# ShematicPCB.net
KiCad netlist of a schematic drawn in EAGLE
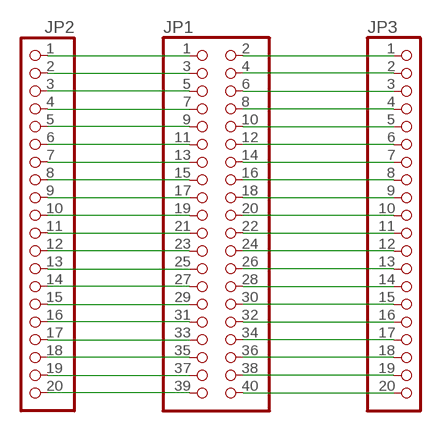
[diagram p0: schematic, sheet 1]

(export (version "E")
  (design (tool "Eeschema 10.0.6"))
  (components
    (comp (ref "JP1")
      (value "PINHD-2X20")
      (footprint "eagle-import:2X20")
      (libsource (lib "eagle-import") (part "PINHD-2X20"))
    )
    (comp (ref "JP2")
      (value "PINHD-1X20")
      (footprint "eagle-import:1X20")
      (libsource (lib "eagle-import") (part "PINHD-1X20"))
    )
    (comp (ref "JP3")
      (value "PINHD-1X20")
      (footprint "eagle-import:1X20")
      (libsource (lib "eagle-import") (part "PINHD-1X20"))
    )
  )
  (nets
    (net (code "1") (name "Net-(JP1-Pad1)") (class "Default")
      (node (ref "JP1") (pin "1") (pinfunction "1_1") (pintype "passive"))
      (node (ref "JP2") (pin "1") (pinfunction "1_1") (pintype "passive"))
    )
    (net (code "2") (name "Net-(JP1-Pad2)") (class "Default")
      (node (ref "JP1") (pin "2") (pinfunction "2_2") (pintype "passive"))
      (node (ref "JP3") (pin "1") (pinfunction "1_1") (pintype "passive"))
    )
    (net (code "3") (name "Net-(JP1-Pad3)") (class "Default")
      (node (ref "JP1") (pin "3") (pinfunction "3_3") (pintype "passive"))
      (node (ref "JP2") (pin "2") (pinfunction "2_2") (pintype "passive"))
    )
    (net (code "4") (name "Net-(JP1-Pad4)") (class "Default")
      (node (ref "JP1") (pin "4") (pinfunction "4_4") (pintype "passive"))
      (node (ref "JP3") (pin "2") (pinfunction "2_2") (pintype "passive"))
    )
    (net (code "5") (name "Net-(JP1-Pad5)") (class "Default")
      (node (ref "JP1") (pin "5") (pinfunction "5_5") (pintype "passive"))
      (node (ref "JP2") (pin "3") (pinfunction "3_3") (pintype "passive"))
    )
    (net (code "6") (name "Net-(JP1-Pad6)") (class "Default")
      (node (ref "JP1") (pin "6") (pinfunction "6_6") (pintype "passive"))
      (node (ref "JP3") (pin "3") (pinfunction "3_3") (pintype "passive"))
    )
    (net (code "7") (name "Net-(JP1-Pad7)") (class "Default")
      (node (ref "JP1") (pin "7") (pinfunction "7_7") (pintype "passive"))
      (node (ref "JP2") (pin "4") (pinfunction "4_4") (pintype "passive"))
    )
    (net (code "8") (name "Net-(JP1-Pad8)") (class "Default")
      (node (ref "JP1") (pin "8") (pinfunction "8_8") (pintype "passive"))
      (node (ref "JP3") (pin "4") (pinfunction "4_4") (pintype "passive"))
    )
    (net (code "9") (name "Net-(JP1-Pad9)") (class "Default")
      (node (ref "JP1") (pin "9") (pinfunction "9_9") (pintype "passive"))
      (node (ref "JP2") (pin "5") (pinfunction "5_5") (pintype "passive"))
    )
    (net (code "10") (name "Net-(JP1-Pad10)") (class "Default")
      (node (ref "JP1") (pin "10") (pinfunction "10_10") (pintype "passive"))
      (node (ref "JP3") (pin "5") (pinfunction "5_5") (pintype "passive"))
    )
    (net (code "11") (name "Net-(JP1-Pad11)") (class "Default")
      (node (ref "JP1") (pin "11") (pinfunction "11_11") (pintype "passive"))
      (node (ref "JP2") (pin "6") (pinfunction "6_6") (pintype "passive"))
    )
    (net (code "12") (name "Net-(JP1-Pad12)") (class "Default")
      (node (ref "JP1") (pin "12") (pinfunction "12_12") (pintype "passive"))
      (node (ref "JP3") (pin "6") (pinfunction "6_6") (pintype "passive"))
    )
    (net (code "13") (name "Net-(JP1-Pad13)") (class "Default")
      (node (ref "JP1") (pin "13") (pinfunction "13_13") (pintype "passive"))
      (node (ref "JP2") (pin "7") (pinfunction "7_7") (pintype "passive"))
    )
    (net (code "14") (name "Net-(JP1-Pad14)") (class "Default")
      (node (ref "JP1") (pin "14") (pinfunction "14_14") (pintype "passive"))
      (node (ref "JP3") (pin "7") (pinfunction "7_7") (pintype "passive"))
    )
    (net (code "15") (name "Net-(JP1-Pad15)") (class "Default")
      (node (ref "JP1") (pin "15") (pinfunction "15_15") (pintype "passive"))
      (node (ref "JP2") (pin "8") (pinfunction "8_8") (pintype "passive"))
    )
    (net (code "16") (name "Net-(JP1-Pad16)") (class "Default")
      (node (ref "JP1") (pin "16") (pinfunction "16_16") (pintype "passive"))
      (node (ref "JP3") (pin "8") (pinfunction "8_8") (pintype "passive"))
    )
    (net (code "17") (name "Net-(JP1-Pad17)") (class "Default")
      (node (ref "JP1") (pin "17") (pinfunction "17_17") (pintype "passive"))
      (node (ref "JP2") (pin "9") (pinfunction "9_9") (pintype "passive"))
    )
    (net (code "18") (name "Net-(JP1-Pad18)") (class "Default")
      (node (ref "JP1") (pin "18") (pinfunction "18_18") (pintype "passive"))
      (node (ref "JP3") (pin "9") (pinfunction "9_9") (pintype "passive"))
    )
    (net (code "19") (name "Net-(JP1-Pad19)") (class "Default")
      (node (ref "JP1") (pin "19") (pinfunction "19_19") (pintype "passive"))
      (node (ref "JP2") (pin "10") (pinfunction "10_10") (pintype "passive"))
    )
    (net (code "20") (name "Net-(JP1-Pad20)") (class "Default")
      (node (ref "JP1") (pin "20") (pinfunction "20_20") (pintype "passive"))
      (node (ref "JP3") (pin "10") (pinfunction "10_10") (pintype "passive"))
    )
    (net (code "21") (name "Net-(JP1-Pad21)") (class "Default")
      (node (ref "JP1") (pin "21") (pinfunction "21_21") (pintype "passive"))
      (node (ref "JP2") (pin "11") (pinfunction "11_11") (pintype "passive"))
    )
    (net (code "22") (name "Net-(JP1-Pad22)") (class "Default")
      (node (ref "JP1") (pin "22") (pinfunction "22_22") (pintype "passive"))
      (node (ref "JP3") (pin "11") (pinfunction "11_11") (pintype "passive"))
    )
    (net (code "23") (name "Net-(JP1-Pad23)") (class "Default")
      (node (ref "JP1") (pin "23") (pinfunction "23_23") (pintype "passive"))
      (node (ref "JP2") (pin "12") (pinfunction "12_12") (pintype "passive"))
    )
    (net (code "24") (name "Net-(JP1-Pad24)") (class "Default")
      (node (ref "JP1") (pin "24") (pinfunction "24_24") (pintype "passive"))
      (node (ref "JP3") (pin "12") (pinfunction "12_12") (pintype "passive"))
    )
    (net (code "25") (name "Net-(JP1-Pad25)") (class "Default")
      (node (ref "JP1") (pin "25") (pinfunction "25_25") (pintype "passive"))
      (node (ref "JP2") (pin "13") (pinfunction "13_13") (pintype "passive"))
    )
    (net (code "26") (name "Net-(JP1-Pad26)") (class "Default")
      (node (ref "JP1") (pin "26") (pinfunction "26_26") (pintype "passive"))
      (node (ref "JP3") (pin "13") (pinfunction "13_13") (pintype "passive"))
    )
    (net (code "27") (name "Net-(JP1-Pad27)") (class "Default")
      (node (ref "JP1") (pin "27") (pinfunction "27_27") (pintype "passive"))
      (node (ref "JP2") (pin "14") (pinfunction "14_14") (pintype "passive"))
    )
    (net (code "28") (name "Net-(JP1-Pad28)") (class "Default")
      (node (ref "JP1") (pin "28") (pinfunction "28_28") (pintype "passive"))
      (node (ref "JP3") (pin "14") (pinfunction "14_14") (pintype "passive"))
    )
    (net (code "29") (name "Net-(JP1-Pad29)") (class "Default")
      (node (ref "JP1") (pin "29") (pinfunction "29_29") (pintype "passive"))
      (node (ref "JP2") (pin "15") (pinfunction "15_15") (pintype "passive"))
    )
    (net (code "30") (name "Net-(JP1-Pad30)") (class "Default")
      (node (ref "JP1") (pin "30") (pinfunction "30_30") (pintype "passive"))
      (node (ref "JP3") (pin "15") (pinfunction "15_15") (pintype "passive"))
    )
    (net (code "31") (name "Net-(JP1-Pad31)") (class "Default")
      (node (ref "JP1") (pin "31") (pinfunction "31_31") (pintype "passive"))
      (node (ref "JP2") (pin "16") (pinfunction "16_16") (pintype "passive"))
    )
    (net (code "32") (name "Net-(JP1-Pad32)") (class "Default")
      (node (ref "JP1") (pin "32") (pinfunction "32_32") (pintype "passive"))
      (node (ref "JP3") (pin "16") (pinfunction "16_16") (pintype "passive"))
    )
    (net (code "33") (name "Net-(JP1-Pad33)") (class "Default")
      (node (ref "JP1") (pin "33") (pinfunction "33_33") (pintype "passive"))
      (node (ref "JP2") (pin "17") (pinfunction "17_17") (pintype "passive"))
    )
    (net (code "34") (name "Net-(JP1-Pad34)") (class "Default")
      (node (ref "JP1") (pin "34") (pinfunction "34_34") (pintype "passive"))
      (node (ref "JP3") (pin "17") (pinfunction "17_17") (pintype "passive"))
    )
    (net (code "35") (name "Net-(JP1-Pad35)") (class "Default")
      (node (ref "JP1") (pin "35") (pinfunction "35_35") (pintype "passive"))
      (node (ref "JP2") (pin "18") (pinfunction "18_18") (pintype "passive"))
    )
    (net (code "36") (name "Net-(JP1-Pad36)") (class "Default")
      (node (ref "JP1") (pin "36") (pinfunction "36_36") (pintype "passive"))
      (node (ref "JP3") (pin "18") (pinfunction "18_18") (pintype "passive"))
    )
    (net (code "37") (name "Net-(JP1-Pad37)") (class "Default")
      (node (ref "JP1") (pin "37") (pinfunction "37_37") (pintype "passive"))
      (node (ref "JP2") (pin "19") (pinfunction "19_19") (pintype "passive"))
    )
    (net (code "38") (name "Net-(JP1-Pad38)") (class "Default")
      (node (ref "JP1") (pin "38") (pinfunction "38_38") (pintype "passive"))
      (node (ref "JP3") (pin "19") (pinfunction "19_19") (pintype "passive"))
    )
    (net (code "39") (name "Net-(JP1-Pad39)") (class "Default")
      (node (ref "JP1") (pin "39") (pinfunction "39_39") (pintype "passive"))
      (node (ref "JP2") (pin "20") (pinfunction "20_20") (pintype "passive"))
    )
    (net (code "40") (name "Net-(JP1-Pad40)") (class "Default")
      (node (ref "JP1") (pin "40") (pinfunction "40_40") (pintype "passive"))
      (node (ref "JP3") (pin "20") (pinfunction "20_20") (pintype "passive"))
    )
  )
)
